# 20203101_second_Platine_Power.net
KiCad netlist of a schematic drawn in EAGLE
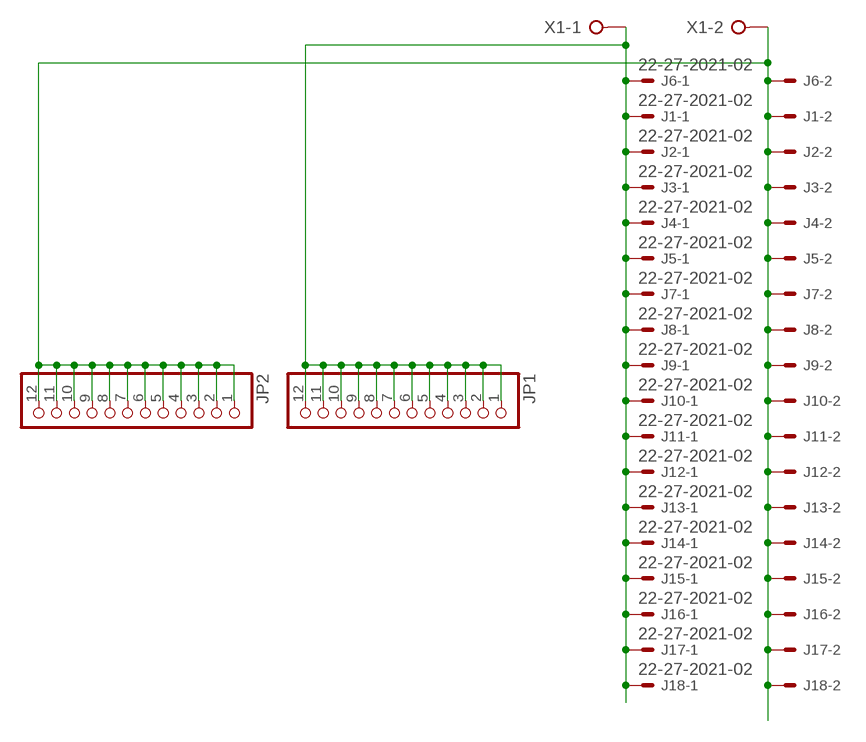
[diagram p0: schematic, sheet 1]

(export (version "E")
  (design (tool "Eeschema 10.0.6"))
  (components
    (comp (ref "J1")
      (value "22-27-2021-02")
      (footprint "eagle-import:6410-02")
      (libsource (lib "eagle-import") (part "22-?-0227-2021"))
    )
    (comp (ref "J2")
      (value "22-27-2021-02")
      (footprint "eagle-import:6410-02")
      (libsource (lib "eagle-import") (part "22-?-0227-2021"))
    )
    (comp (ref "J3")
      (value "22-27-2021-02")
      (footprint "eagle-import:6410-02")
      (libsource (lib "eagle-import") (part "22-?-0227-2021"))
    )
    (comp (ref "J4")
      (value "22-27-2021-02")
      (footprint "eagle-import:6410-02")
      (libsource (lib "eagle-import") (part "22-?-0227-2021"))
    )
    (comp (ref "J5")
      (value "22-27-2021-02")
      (footprint "eagle-import:6410-02")
      (libsource (lib "eagle-import") (part "22-?-0227-2021"))
    )
    (comp (ref "J6")
      (value "22-27-2021-02")
      (footprint "eagle-import:6410-02")
      (libsource (lib "eagle-import") (part "22-?-0227-2021"))
    )
    (comp (ref "J7")
      (value "22-27-2021-02")
      (footprint "eagle-import:6410-02")
      (libsource (lib "eagle-import") (part "22-?-0227-2021"))
    )
    (comp (ref "J8")
      (value "22-27-2021-02")
      (footprint "eagle-import:6410-02")
      (libsource (lib "eagle-import") (part "22-?-0227-2021"))
    )
    (comp (ref "J9")
      (value "22-27-2021-02")
      (footprint "eagle-import:6410-02")
      (libsource (lib "eagle-import") (part "22-?-0227-2021"))
    )
    (comp (ref "J10")
      (value "22-27-2021-02")
      (footprint "eagle-import:6410-02")
      (libsource (lib "eagle-import") (part "22-?-0227-2021"))
    )
    (comp (ref "J11")
      (value "22-27-2021-02")
      (footprint "eagle-import:6410-02")
      (libsource (lib "eagle-import") (part "22-?-0227-2021"))
    )
    (comp (ref "J12")
      (value "22-27-2021-02")
      (footprint "eagle-import:6410-02")
      (libsource (lib "eagle-import") (part "22-?-0227-2021"))
    )
    (comp (ref "J13")
      (value "22-27-2021-02")
      (footprint "eagle-import:6410-02")
      (libsource (lib "eagle-import") (part "22-?-0227-2021"))
    )
    (comp (ref "J14")
      (value "22-27-2021-02")
      (footprint "eagle-import:6410-02")
      (libsource (lib "eagle-import") (part "22-?-0227-2021"))
    )
    (comp (ref "J15")
      (value "22-27-2021-02")
      (footprint "eagle-import:6410-02")
      (libsource (lib "eagle-import") (part "22-?-0227-2021"))
    )
    (comp (ref "J16")
      (value "22-27-2021-02")
      (footprint "eagle-import:6410-02")
      (libsource (lib "eagle-import") (part "22-?-0227-2021"))
    )
    (comp (ref "J17")
      (value "22-27-2021-02")
      (footprint "eagle-import:6410-02")
      (libsource (lib "eagle-import") (part "22-?-0227-2021"))
    )
    (comp (ref "J18")
      (value "22-27-2021-02")
      (footprint "eagle-import:6410-02")
      (libsource (lib "eagle-import") (part "22-?-0227-2021"))
    )
    (comp (ref "JP1")
      (value "PINHD-1X12")
      (footprint "eagle-import:1X12")
      (libsource (lib "eagle-import") (part "PINHD-1X12"))
    )
    (comp (ref "JP2")
      (value "PINHD-1X12")
      (footprint "eagle-import:1X12")
      (libsource (lib "eagle-import") (part "PINHD-1X12"))
    )
    (comp (ref "X1")
      (value "W237-02P")
      (footprint "eagle-import:W237-132")
      (libsource (lib "eagle-import") (part "W237-02P"))
    )
  )
  (nets
    (net (code "1") (name "Net-(J10A-S)") (class "Default")
      (node (ref "J1") (pin "1") (pinfunction "S_1") (pintype "passive"))
      (node (ref "J10") (pin "1") (pinfunction "S_1") (pintype "passive"))
      (node (ref "J11") (pin "1") (pinfunction "S_1") (pintype "passive"))
      (node (ref "J12") (pin "1") (pinfunction "S_1") (pintype "passive"))
      (node (ref "J13") (pin "1") (pinfunction "S_1") (pintype "passive"))
      (node (ref "J14") (pin "1") (pinfunction "S_1") (pintype "passive"))
      (node (ref "J15") (pin "1") (pinfunction "S_1") (pintype "passive"))
      (node (ref "J16") (pin "1") (pinfunction "S_1") (pintype "passive"))
      (node (ref "J17") (pin "1") (pinfunction "S_1") (pintype "passive"))
      (node (ref "J18") (pin "1") (pinfunction "S_1") (pintype "passive"))
      (node (ref "J2") (pin "1") (pinfunction "S_1") (pintype "passive"))
      (node (ref "J3") (pin "1") (pinfunction "S_1") (pintype "passive"))
      (node (ref "J4") (pin "1") (pinfunction "S_1") (pintype "passive"))
      (node (ref "J5") (pin "1") (pinfunction "S_1") (pintype "passive"))
      (node (ref "J6") (pin "1") (pinfunction "S_1") (pintype "passive"))
      (node (ref "J7") (pin "1") (pinfunction "S_1") (pintype "passive"))
      (node (ref "J8") (pin "1") (pinfunction "S_1") (pintype "passive"))
      (node (ref "J9") (pin "1") (pinfunction "S_1") (pintype "passive"))
      (node (ref "JP1") (pin "1") (pinfunction "1_1") (pintype "passive"))
      (node (ref "JP1") (pin "10") (pinfunction "10_10") (pintype "passive"))
      (node (ref "JP1") (pin "11") (pinfunction "11_11") (pintype "passive"))
      (node (ref "JP1") (pin "12") (pinfunction "12_12") (pintype "passive"))
      (node (ref "JP1") (pin "2") (pinfunction "2_2") (pintype "passive"))
      (node (ref "JP1") (pin "3") (pinfunction "3_3") (pintype "passive"))
      (node (ref "JP1") (pin "4") (pinfunction "4_4") (pintype "passive"))
      (node (ref "JP1") (pin "5") (pinfunction "5_5") (pintype "passive"))
      (node (ref "JP1") (pin "6") (pinfunction "6_6") (pintype "passive"))
      (node (ref "JP1") (pin "7") (pinfunction "7_7") (pintype "passive"))
      (node (ref "JP1") (pin "8") (pinfunction "8_8") (pintype "passive"))
      (node (ref "JP1") (pin "9") (pinfunction "9_9") (pintype "passive"))
      (node (ref "X1") (pin "1") (pinfunction "KL_1") (pintype "passive"))
    )
    (net (code "2") (name "Net-(J10B-S)") (class "Default")
      (node (ref "J1") (pin "2") (pinfunction "S_2") (pintype "passive"))
      (node (ref "J10") (pin "2") (pinfunction "S_2") (pintype "passive"))
      (node (ref "J11") (pin "2") (pinfunction "S_2") (pintype "passive"))
      (node (ref "J12") (pin "2") (pinfunction "S_2") (pintype "passive"))
      (node (ref "J13") (pin "2") (pinfunction "S_2") (pintype "passive"))
      (node (ref "J14") (pin "2") (pinfunction "S_2") (pintype "passive"))
      (node (ref "J15") (pin "2") (pinfunction "S_2") (pintype "passive"))
      (node (ref "J16") (pin "2") (pinfunction "S_2") (pintype "passive"))
      (node (ref "J17") (pin "2") (pinfunction "S_2") (pintype "passive"))
      (node (ref "J18") (pin "2") (pinfunction "S_2") (pintype "passive"))
      (node (ref "J2") (pin "2") (pinfunction "S_2") (pintype "passive"))
      (node (ref "J3") (pin "2") (pinfunction "S_2") (pintype "passive"))
      (node (ref "J4") (pin "2") (pinfunction "S_2") (pintype "passive"))
      (node (ref "J5") (pin "2") (pinfunction "S_2") (pintype "passive"))
      (node (ref "J6") (pin "2") (pinfunction "S_2") (pintype "passive"))
      (node (ref "J7") (pin "2") (pinfunction "S_2") (pintype "passive"))
      (node (ref "J8") (pin "2") (pinfunction "S_2") (pintype "passive"))
      (node (ref "J9") (pin "2") (pinfunction "S_2") (pintype "passive"))
      (node (ref "JP2") (pin "1") (pinfunction "1_1") (pintype "passive"))
      (node (ref "JP2") (pin "10") (pinfunction "10_10") (pintype "passive"))
      (node (ref "JP2") (pin "11") (pinfunction "11_11") (pintype "passive"))
      (node (ref "JP2") (pin "12") (pinfunction "12_12") (pintype "passive"))
      (node (ref "JP2") (pin "2") (pinfunction "2_2") (pintype "passive"))
      (node (ref "JP2") (pin "3") (pinfunction "3_3") (pintype "passive"))
      (node (ref "JP2") (pin "4") (pinfunction "4_4") (pintype "passive"))
      (node (ref "JP2") (pin "5") (pinfunction "5_5") (pintype "passive"))
      (node (ref "JP2") (pin "6") (pinfunction "6_6") (pintype "passive"))
      (node (ref "JP2") (pin "7") (pinfunction "7_7") (pintype "passive"))
      (node (ref "JP2") (pin "8") (pinfunction "8_8") (pintype "passive"))
      (node (ref "JP2") (pin "9") (pinfunction "9_9") (pintype "passive"))
      (node (ref "X1") (pin "2") (pinfunction "KL_2") (pintype "passive"))
    )
  )
)
